# CLK_HMC7043.net
KiCad netlist of a schematic drawn in Altium Designer
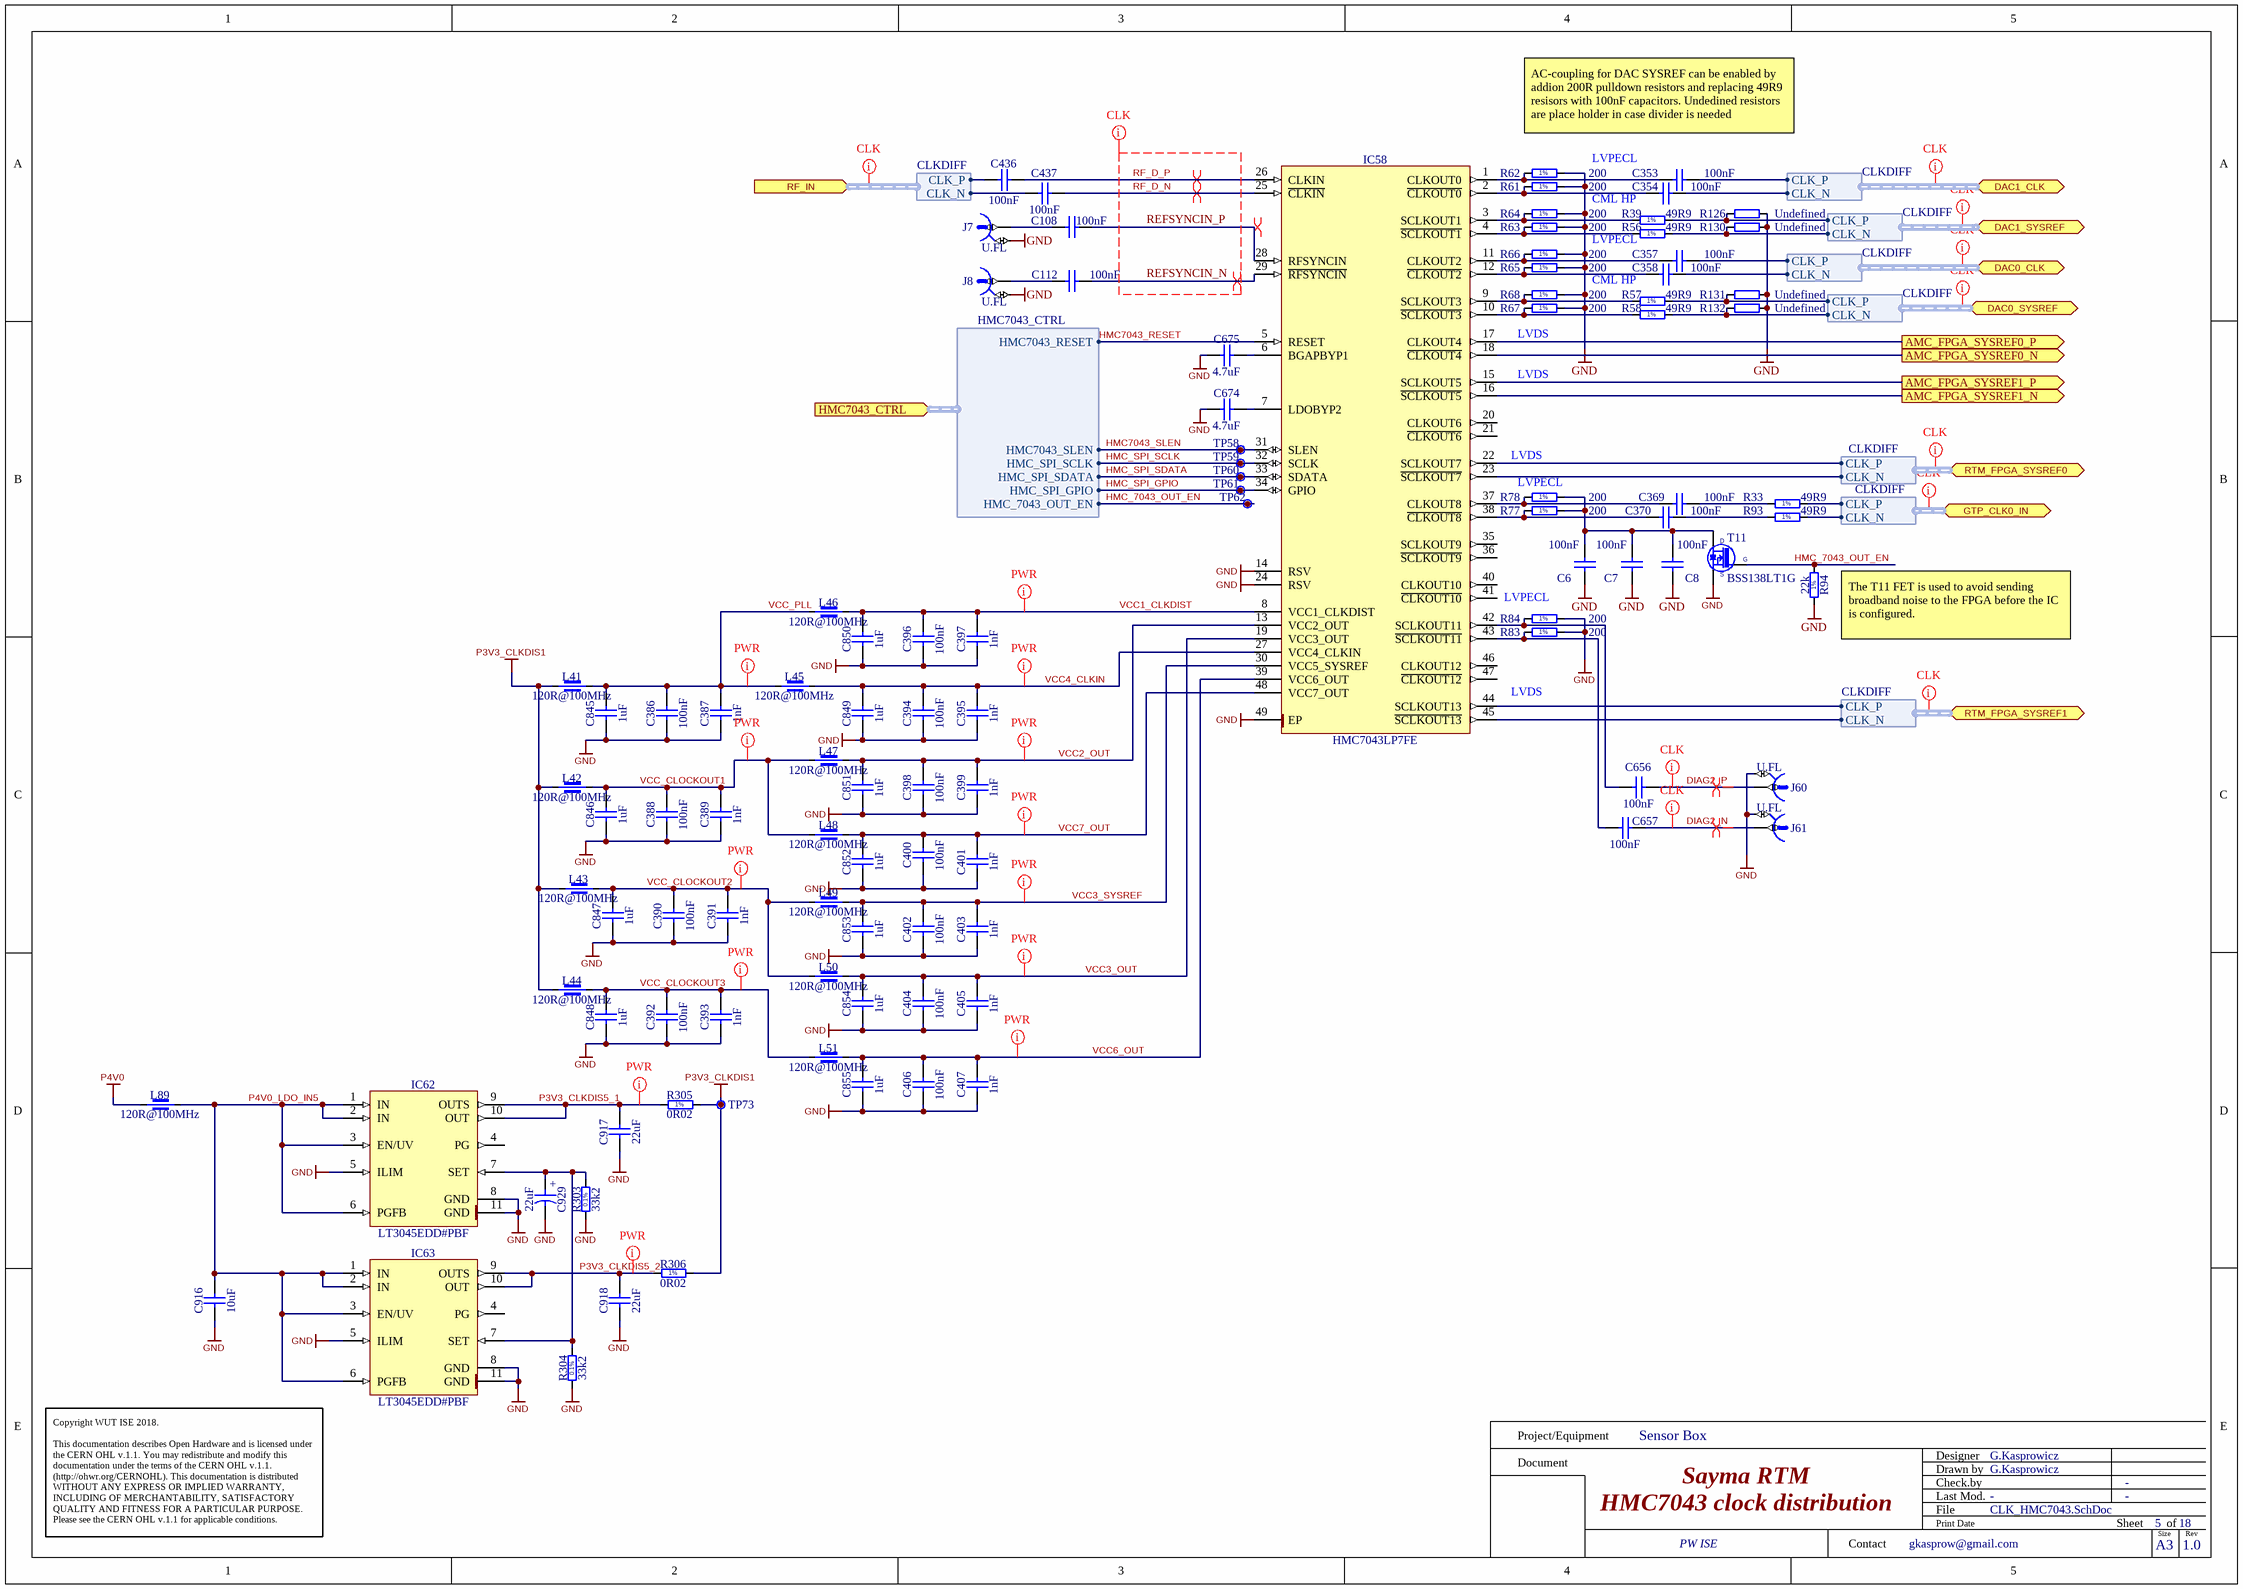
[diagram p0: CLK_HMC7043.SchDoc]

(export (version "E")
  (design (tool "Eeschema 10.0.6"))
  (components
    (comp (ref "C6")
      (value "100nF")
      (footprint "CAPC0603X33N")
      (description "Non-polarised capacitor")
      (fields
        (field (name "MANUFACTURER PART NUMBER") "CC0201_100NF_6.3V_10%_X5R")
        (field (name "MANUFACTURER") "GENERIC")
        (field (name "AUTHOR") "CERN DEM JLC")
      )
      (libsource (lib "Capacitors") (part "Capacitor - non polarized"))
    )
    (comp (ref "C7")
      (value "100nF")
      (footprint "CAPC0603X33N")
      (description "Non-polarised capacitor")
      (fields
        (field (name "MANUFACTURER PART NUMBER") "CC0201_100NF_6.3V_10%_X5R")
        (field (name "MANUFACTURER") "GENERIC")
        (field (name "AUTHOR") "CERN DEM JLC")
      )
      (libsource (lib "Capacitors") (part "Capacitor - non polarized"))
    )
    (comp (ref "C8")
      (value "100nF")
      (footprint "CAPC0603X33N")
      (description "Non-polarised capacitor")
      (fields
        (field (name "MANUFACTURER PART NUMBER") "CC0201_100NF_6.3V_10%_X5R")
        (field (name "MANUFACTURER") "GENERIC")
        (field (name "AUTHOR") "CERN DEM JLC")
      )
      (libsource (lib "Capacitors") (part "Capacitor - non polarized"))
    )
    (comp (ref "C108")
      (value "100nF")
      (footprint "CAPC0603X33N")
      (description "Non-polarised capacitor")
      (fields
        (field (name "MANUFACTURER PART NUMBER") "CC0201_100NF_6.3V_10%_X5R")
        (field (name "MANUFACTURER") "GENERIC")
        (field (name "AUTHOR") "CERN DEM JLC")
      )
      (libsource (lib "Capacitors") (part "Capacitor - non polarized"))
    )
    (comp (ref "C112")
      (value "100nF")
      (footprint "CAPC0603X33N")
      (description "Non-polarised capacitor")
      (fields
        (field (name "MANUFACTURER PART NUMBER") "CC0201_100NF_6.3V_10%_X5R")
        (field (name "MANUFACTURER") "GENERIC")
        (field (name "AUTHOR") "CERN DEM JLC")
      )
      (libsource (lib "Capacitors") (part "Capacitor - non polarized"))
    )
    (comp (ref "C353")
      (value "100nF")
      (footprint "CAPC0603X33N")
      (description "Non-polarised capacitor")
      (fields
        (field (name "MANUFACTURER PART NUMBER") "CC0201_100NF_6.3V_10%_X5R")
        (field (name "MANUFACTURER") "GENERIC")
        (field (name "AUTHOR") "CERN DEM JLC")
      )
      (libsource (lib "Capacitors") (part "Capacitor - non polarized"))
    )
    (comp (ref "C354")
      (value "100nF")
      (footprint "CAPC0603X33N")
      (description "Non-polarised capacitor")
      (fields
        (field (name "MANUFACTURER PART NUMBER") "CC0201_100NF_6.3V_10%_X5R")
        (field (name "MANUFACTURER") "GENERIC")
        (field (name "AUTHOR") "CERN DEM JLC")
      )
      (libsource (lib "Capacitors") (part "Capacitor - non polarized"))
    )
    (comp (ref "C357")
      (value "100nF")
      (footprint "CAPC0603X33N")
      (description "Non-polarised capacitor")
      (fields
        (field (name "MANUFACTURER PART NUMBER") "CC0201_100NF_6.3V_10%_X5R")
        (field (name "MANUFACTURER") "GENERIC")
        (field (name "AUTHOR") "CERN DEM JLC")
      )
      (libsource (lib "Capacitors") (part "Capacitor - non polarized"))
    )
    (comp (ref "C358")
      (value "100nF")
      (footprint "CAPC0603X33N")
      (description "Non-polarised capacitor")
      (fields
        (field (name "MANUFACTURER PART NUMBER") "CC0201_100NF_6.3V_10%_X5R")
        (field (name "MANUFACTURER") "GENERIC")
        (field (name "AUTHOR") "CERN DEM JLC")
      )
      (libsource (lib "Capacitors") (part "Capacitor - non polarized"))
    )
    (comp (ref "C369")
      (value "100nF")
      (footprint "CAPC0603X33N")
      (description "Non-polarised capacitor")
      (fields
        (field (name "MANUFACTURER PART NUMBER") "CC0201_100NF_6.3V_10%_X5R")
        (field (name "MANUFACTURER") "GENERIC")
        (field (name "AUTHOR") "CERN DEM JLC")
      )
      (libsource (lib "Capacitors") (part "Capacitor - non polarized"))
    )
    (comp (ref "C370")
      (value "100nF")
      (footprint "CAPC0603X33N")
      (description "Non-polarised capacitor")
      (fields
        (field (name "MANUFACTURER PART NUMBER") "CC0201_100NF_6.3V_10%_X5R")
        (field (name "MANUFACTURER") "GENERIC")
        (field (name "AUTHOR") "CERN DEM JLC")
      )
      (libsource (lib "Capacitors") (part "Capacitor - non polarized"))
    )
    (comp (ref "C386")
      (value "100nF")
      (footprint "CAPC0603X33N")
      (description "Non-polarised capacitor")
      (fields
        (field (name "MANUFACTURER PART NUMBER") "CC0201_100NF_6.3V_10%_X5R")
        (field (name "MANUFACTURER") "GENERIC")
        (field (name "AUTHOR") "CERN DEM JLC")
      )
      (libsource (lib "Capacitors") (part "Capacitor - non polarized"))
    )
    (comp (ref "C387")
      (value "1nF")
      (footprint "CAPC0603X33N")
      (description "Non-polarised capacitor")
      (fields
        (field (name "MANUFACTURER PART NUMBER") "CC0201_1NF_16V_10%_X5R")
        (field (name "MANUFACTURER") "GENERIC")
        (field (name "AUTHOR") "CERN DEM JLC")
      )
      (libsource (lib "Capacitors") (part "Capacitor - non polarized"))
    )
    (comp (ref "C388")
      (value "100nF")
      (footprint "CAPC0603X33N")
      (description "Non-polarised capacitor")
      (fields
        (field (name "MANUFACTURER PART NUMBER") "CC0201_100NF_6.3V_10%_X5R")
        (field (name "MANUFACTURER") "GENERIC")
        (field (name "AUTHOR") "CERN DEM JLC")
      )
      (libsource (lib "Capacitors") (part "Capacitor - non polarized"))
    )
    (comp (ref "C389")
      (value "1nF")
      (footprint "CAPC0603X33N")
      (description "Non-polarised capacitor")
      (fields
        (field (name "MANUFACTURER PART NUMBER") "CC0201_1NF_16V_10%_X5R")
        (field (name "MANUFACTURER") "GENERIC")
        (field (name "AUTHOR") "CERN DEM JLC")
      )
      (libsource (lib "Capacitors") (part "Capacitor - non polarized"))
    )
    (comp (ref "C390")
      (value "100nF")
      (footprint "CAPC0603X33N")
      (description "Non-polarised capacitor")
      (fields
        (field (name "MANUFACTURER PART NUMBER") "CC0201_100NF_6.3V_10%_X5R")
        (field (name "MANUFACTURER") "GENERIC")
        (field (name "AUTHOR") "CERN DEM JLC")
      )
      (libsource (lib "Capacitors") (part "Capacitor - non polarized"))
    )
    (comp (ref "C391")
      (value "1nF")
      (footprint "CAPC0603X33N")
      (description "Non-polarised capacitor")
      (fields
        (field (name "MANUFACTURER PART NUMBER") "CC0201_1NF_16V_10%_X5R")
        (field (name "MANUFACTURER") "GENERIC")
        (field (name "AUTHOR") "CERN DEM JLC")
      )
      (libsource (lib "Capacitors") (part "Capacitor - non polarized"))
    )
    (comp (ref "C392")
      (value "100nF")
      (footprint "CAPC0603X33N")
      (description "Non-polarised capacitor")
      (fields
        (field (name "MANUFACTURER PART NUMBER") "CC0201_100NF_6.3V_10%_X5R")
        (field (name "MANUFACTURER") "GENERIC")
        (field (name "AUTHOR") "CERN DEM JLC")
      )
      (libsource (lib "Capacitors") (part "Capacitor - non polarized"))
    )
    (comp (ref "C393")
      (value "1nF")
      (footprint "CAPC0603X33N")
      (description "Non-polarised capacitor")
      (fields
        (field (name "MANUFACTURER PART NUMBER") "CC0201_1NF_16V_10%_X5R")
        (field (name "MANUFACTURER") "GENERIC")
        (field (name "AUTHOR") "CERN DEM JLC")
      )
      (libsource (lib "Capacitors") (part "Capacitor - non polarized"))
    )
    (comp (ref "C394")
      (value "100nF")
      (footprint "CAPC0603X33N")
      (description "Non-polarised capacitor")
      (fields
        (field (name "MANUFACTURER PART NUMBER") "CC0201_100NF_6.3V_10%_X5R")
        (field (name "MANUFACTURER") "GENERIC")
        (field (name "AUTHOR") "CERN DEM JLC")
      )
      (libsource (lib "Capacitors") (part "Capacitor - non polarized"))
    )
    (comp (ref "C395")
      (value "1nF")
      (footprint "CAPC0603X33N")
      (description "Non-polarised capacitor")
      (fields
        (field (name "MANUFACTURER PART NUMBER") "CC0201_1NF_16V_10%_X5R")
        (field (name "MANUFACTURER") "GENERIC")
        (field (name "AUTHOR") "CERN DEM JLC")
      )
      (libsource (lib "Capacitors") (part "Capacitor - non polarized"))
    )
    (comp (ref "C396")
      (value "100nF")
      (footprint "CAPC0603X33N")
      (description "Non-polarised capacitor")
      (fields
        (field (name "MANUFACTURER PART NUMBER") "CC0201_100NF_6.3V_10%_X5R")
        (field (name "MANUFACTURER") "GENERIC")
        (field (name "AUTHOR") "CERN DEM JLC")
      )
      (libsource (lib "Capacitors") (part "Capacitor - non polarized"))
    )
    (comp (ref "C397")
      (value "1nF")
      (footprint "CAPC0603X33N")
      (description "Non-polarised capacitor")
      (fields
        (field (name "MANUFACTURER PART NUMBER") "CC0201_1NF_16V_10%_X5R")
        (field (name "MANUFACTURER") "GENERIC")
        (field (name "AUTHOR") "CERN DEM JLC")
      )
      (libsource (lib "Capacitors") (part "Capacitor - non polarized"))
    )
    (comp (ref "C398")
      (value "100nF")
      (footprint "CAPC0603X33N")
      (description "Non-polarised capacitor")
      (fields
        (field (name "MANUFACTURER PART NUMBER") "CC0201_100NF_6.3V_10%_X5R")
        (field (name "MANUFACTURER") "GENERIC")
        (field (name "AUTHOR") "CERN DEM JLC")
      )
      (libsource (lib "Capacitors") (part "Capacitor - non polarized"))
    )
    (comp (ref "C399")
      (value "1nF")
      (footprint "CAPC0603X33N")
      (description "Non-polarised capacitor")
      (fields
        (field (name "MANUFACTURER PART NUMBER") "CC0201_1NF_16V_10%_X5R")
        (field (name "MANUFACTURER") "GENERIC")
        (field (name "AUTHOR") "CERN DEM JLC")
      )
      (libsource (lib "Capacitors") (part "Capacitor - non polarized"))
    )
    (comp (ref "C400")
      (value "100nF")
      (footprint "CAPC0603X33N")
      (description "Non-polarised capacitor")
      (fields
        (field (name "MANUFACTURER PART NUMBER") "CC0201_100NF_6.3V_10%_X5R")
        (field (name "MANUFACTURER") "GENERIC")
        (field (name "AUTHOR") "CERN DEM JLC")
      )
      (libsource (lib "Capacitors") (part "Capacitor - non polarized"))
    )
    (comp (ref "C401")
      (value "1nF")
      (footprint "CAPC0603X33N")
      (description "Non-polarised capacitor")
      (fields
        (field (name "MANUFACTURER PART NUMBER") "CC0201_1NF_16V_10%_X5R")
        (field (name "MANUFACTURER") "GENERIC")
        (field (name "AUTHOR") "CERN DEM JLC")
      )
      (libsource (lib "Capacitors") (part "Capacitor - non polarized"))
    )
    (comp (ref "C402")
      (value "100nF")
      (footprint "CAPC0603X33N")
      (description "Non-polarised capacitor")
      (fields
        (field (name "MANUFACTURER PART NUMBER") "CC0201_100NF_6.3V_10%_X5R")
        (field (name "MANUFACTURER") "GENERIC")
        (field (name "AUTHOR") "CERN DEM JLC")
      )
      (libsource (lib "Capacitors") (part "Capacitor - non polarized"))
    )
    (comp (ref "C403")
      (value "1nF")
      (footprint "CAPC0603X33N")
      (description "Non-polarised capacitor")
      (fields
        (field (name "MANUFACTURER PART NUMBER") "CC0201_1NF_16V_10%_X5R")
        (field (name "MANUFACTURER") "GENERIC")
        (field (name "AUTHOR") "CERN DEM JLC")
      )
      (libsource (lib "Capacitors") (part "Capacitor - non polarized"))
    )
    (comp (ref "C404")
      (value "100nF")
      (footprint "CAPC0603X33N")
      (description "Non-polarised capacitor")
      (fields
        (field (name "MANUFACTURER PART NUMBER") "CC0201_100NF_6.3V_10%_X5R")
        (field (name "MANUFACTURER") "GENERIC")
        (field (name "AUTHOR") "CERN DEM JLC")
      )
      (libsource (lib "Capacitors") (part "Capacitor - non polarized"))
    )
    (comp (ref "C405")
      (value "1nF")
      (footprint "CAPC0603X33N")
      (description "Non-polarised capacitor")
      (fields
        (field (name "MANUFACTURER PART NUMBER") "CC0201_1NF_16V_10%_X5R")
        (field (name "MANUFACTURER") "GENERIC")
        (field (name "AUTHOR") "CERN DEM JLC")
      )
      (libsource (lib "Capacitors") (part "Capacitor - non polarized"))
    )
    (comp (ref "C406")
      (value "100nF")
      (footprint "CAPC0603X33N")
      (description "Non-polarised capacitor")
      (fields
        (field (name "MANUFACTURER PART NUMBER") "CC0201_100NF_6.3V_10%_X5R")
        (field (name "MANUFACTURER") "GENERIC")
        (field (name "AUTHOR") "CERN DEM JLC")
      )
      (libsource (lib "Capacitors") (part "Capacitor - non polarized"))
    )
    (comp (ref "C407")
      (value "1nF")
      (footprint "CAPC0603X33N")
      (description "Non-polarised capacitor")
      (fields
        (field (name "MANUFACTURER PART NUMBER") "CC0201_1NF_16V_10%_X5R")
        (field (name "MANUFACTURER") "GENERIC")
        (field (name "AUTHOR") "CERN DEM JLC")
      )
      (libsource (lib "Capacitors") (part "Capacitor - non polarized"))
    )
    (comp (ref "C436")
      (value "100nF")
      (footprint "CAPC0603X33N")
      (description "Non-polarised capacitor")
      (fields
        (field (name "MANUFACTURER PART NUMBER") "CC0201_100NF_6.3V_10%_X5R")
        (field (name "MANUFACTURER") "GENERIC")
        (field (name "AUTHOR") "CERN DEM JLC")
      )
      (libsource (lib "Capacitors") (part "Capacitor - non polarized"))
    )
    (comp (ref "C437")
      (value "100nF")
      (footprint "CAPC0603X33N")
      (description "Non-polarised capacitor")
      (fields
        (field (name "MANUFACTURER PART NUMBER") "CC0201_100NF_6.3V_10%_X5R")
        (field (name "MANUFACTURER") "GENERIC")
        (field (name "AUTHOR") "CERN DEM JLC")
      )
      (libsource (lib "Capacitors") (part "Capacitor - non polarized"))
    )
    (comp (ref "C656")
      (value "100nF")
      (footprint "CAPC0603X33N")
      (description "Non-polarised capacitor")
      (fields
        (field (name "MANUFACTURER PART NUMBER") "CC0201_100NF_6.3V_10%_X5R")
        (field (name "MANUFACTURER") "GENERIC")
        (field (name "AUTHOR") "CERN DEM JLC")
      )
      (libsource (lib "Capacitors") (part "Capacitor - non polarized"))
    )
    (comp (ref "C657")
      (value "100nF")
      (footprint "CAPC0603X33N")
      (description "Non-polarised capacitor")
      (fields
        (field (name "MANUFACTURER PART NUMBER") "CC0201_100NF_6.3V_10%_X5R")
        (field (name "MANUFACTURER") "GENERIC")
        (field (name "AUTHOR") "CERN DEM JLC")
      )
      (libsource (lib "Capacitors") (part "Capacitor - non polarized"))
    )
    (comp (ref "C674")
      (value "4.7uF")
      (footprint "CAPC1608X90N")
      (description "Non-polarised capacitor")
      (fields
        (field (name "MANUFACTURER PART NUMBER") "CC0603_4.7UF_25V_10%_X5R")
        (field (name "MANUFACTURER") "GENERIC")
        (field (name "AUTHOR") "CERN DEM JLC")
      )
      (libsource (lib "Capacitors") (part "Capacitor - non polarized"))
    )
    (comp (ref "C675")
      (value "4.7uF")
      (footprint "CAPC1608X90N")
      (description "Non-polarised capacitor")
      (fields
        (field (name "MANUFACTURER PART NUMBER") "CC0603_4.7UF_25V_10%_X5R")
        (field (name "MANUFACTURER") "GENERIC")
        (field (name "AUTHOR") "CERN DEM JLC")
      )
      (libsource (lib "Capacitors") (part "Capacitor - non polarized"))
    )
    (comp (ref "C845")
      (value "1uF")
      (footprint "CAPC1005X55N")
      (description "Non-polarised capacitor")
      (fields
        (field (name "MANUFACTURER PART NUMBER") "CC0402_1UF_16V_10%_X5R")
        (field (name "MANUFACTURER") "GENERIC")
        (field (name "AUTHOR") "CERN DEM JLC")
      )
      (libsource (lib "Capacitors") (part "Capacitor - non polarized"))
    )
    (comp (ref "C846")
      (value "1uF")
      (footprint "CAPC1005X55N")
      (description "Non-polarised capacitor")
      (fields
        (field (name "MANUFACTURER PART NUMBER") "CC0402_1UF_16V_10%_X5R")
        (field (name "MANUFACTURER") "GENERIC")
        (field (name "AUTHOR") "CERN DEM JLC")
      )
      (libsource (lib "Capacitors") (part "Capacitor - non polarized"))
    )
    (comp (ref "C847")
      (value "1uF")
      (footprint "CAPC1005X55N")
      (description "Non-polarised capacitor")
      (fields
        (field (name "MANUFACTURER PART NUMBER") "CC0402_1UF_16V_10%_X5R")
        (field (name "MANUFACTURER") "GENERIC")
        (field (name "AUTHOR") "CERN DEM JLC")
      )
      (libsource (lib "Capacitors") (part "Capacitor - non polarized"))
    )
    (comp (ref "C848")
      (value "1uF")
      (footprint "CAPC1005X55N")
      (description "Non-polarised capacitor")
      (fields
        (field (name "MANUFACTURER PART NUMBER") "CC0402_1UF_16V_10%_X5R")
        (field (name "MANUFACTURER") "GENERIC")
        (field (name "AUTHOR") "CERN DEM JLC")
      )
      (libsource (lib "Capacitors") (part "Capacitor - non polarized"))
    )
    (comp (ref "C849")
      (value "1uF")
      (footprint "CAPC1005X55N")
      (description "Non-polarised capacitor")
      (fields
        (field (name "MANUFACTURER PART NUMBER") "CC0402_1UF_16V_10%_X5R")
        (field (name "MANUFACTURER") "GENERIC")
        (field (name "AUTHOR") "CERN DEM JLC")
      )
      (libsource (lib "Capacitors") (part "Capacitor - non polarized"))
    )
    (comp (ref "C850")
      (value "1uF")
      (footprint "CAPC1005X55N")
      (description "Non-polarised capacitor")
      (fields
        (field (name "MANUFACTURER PART NUMBER") "CC0402_1UF_16V_10%_X5R")
        (field (name "MANUFACTURER") "GENERIC")
        (field (name "AUTHOR") "CERN DEM JLC")
      )
      (libsource (lib "Capacitors") (part "Capacitor - non polarized"))
    )
    (comp (ref "C851")
      (value "1uF")
      (footprint "CAPC1005X55N")
      (description "Non-polarised capacitor")
      (fields
        (field (name "MANUFACTURER PART NUMBER") "CC0402_1UF_16V_10%_X5R")
        (field (name "MANUFACTURER") "GENERIC")
        (field (name "AUTHOR") "CERN DEM JLC")
      )
      (libsource (lib "Capacitors") (part "Capacitor - non polarized"))
    )
    (comp (ref "C852")
      (value "1uF")
      (footprint "CAPC1005X55N")
      (description "Non-polarised capacitor")
      (fields
        (field (name "MANUFACTURER PART NUMBER") "CC0402_1UF_16V_10%_X5R")
        (field (name "MANUFACTURER") "GENERIC")
        (field (name "AUTHOR") "CERN DEM JLC")
      )
      (libsource (lib "Capacitors") (part "Capacitor - non polarized"))
    )
    (comp (ref "C853")
      (value "1uF")
      (footprint "CAPC1005X55N")
      (description "Non-polarised capacitor")
      (fields
        (field (name "MANUFACTURER PART NUMBER") "CC0402_1UF_16V_10%_X5R")
        (field (name "MANUFACTURER") "GENERIC")
        (field (name "AUTHOR") "CERN DEM JLC")
      )
      (libsource (lib "Capacitors") (part "Capacitor - non polarized"))
    )
    (comp (ref "C854")
      (value "1uF")
      (footprint "CAPC1005X55N")
      (description "Non-polarised capacitor")
      (fields
        (field (name "MANUFACTURER PART NUMBER") "CC0402_1UF_16V_10%_X5R")
        (field (name "MANUFACTURER") "GENERIC")
        (field (name "AUTHOR") "CERN DEM JLC")
      )
      (libsource (lib "Capacitors") (part "Capacitor - non polarized"))
    )
    (comp (ref "C855")
      (value "1uF")
      (footprint "CAPC1005X55N")
      (description "Non-polarised capacitor")
      (fields
        (field (name "MANUFACTURER PART NUMBER") "CC0402_1UF_16V_10%_X5R")
        (field (name "MANUFACTURER") "GENERIC")
        (field (name "AUTHOR") "CERN DEM JLC")
      )
      (libsource (lib "Capacitors") (part "Capacitor - non polarized"))
    )
    (comp (ref "C916")
      (value "10uF")
      (footprint "CAPC1608X87N")
      (description "Non-polarised capacitor")
      (fields
        (field (name "MANUFACTURER PART NUMBER") "CC0603_10uF_6.3V_20%_X5R")
        (field (name "MANUFACTURER") "GENERIC")
        (field (name "AUTHOR") "CERN DEM JLC")
      )
      (libsource (lib "Capacitors") (part "Capacitor - non polarized"))
    )
    (comp (ref "C917")
      (value "22uF")
      (footprint "CAPC2012X135N")
      (description "Non-polarised capacitor")
      (fields
        (field (name "MANUFACTURER PART NUMBER") "CC0805_22UF_16V_10%_X5R")
        (field (name "MANUFACTURER") "GENERIC")
        (field (name "AUTHOR") "CERN DEM JLC")
      )
      (libsource (lib "Capacitors") (part "Capacitor - non polarized"))
    )
    (comp (ref "C918")
      (value "22uF")
      (footprint "CAPC2012X135N")
      (description "Non-polarised capacitor")
      (fields
        (field (name "MANUFACTURER PART NUMBER") "CC0805_22UF_16V_10%_X5R")
        (field (name "MANUFACTURER") "GENERIC")
        (field (name "AUTHOR") "CERN DEM JLC")
      )
      (libsource (lib "Capacitors") (part "Capacitor - non polarized"))
    )
    (comp (ref "C929")
      (value "22uF")
      (footprint "CAPMP3216X180N")
      (description "Polarised capacitor")
      (fields
        (field (name "MANUFACTURER PART NUMBER") "CTE3216-18_22UF_6.3V_10%_LESR0900")
        (field (name "MANUFACTURER") "GENERIC")
        (field (name "AUTHOR") "CERN DEM JLC")
      )
      (libsource (lib "Capacitors") (part "Capacitor - polarized"))
    )
    (comp (ref "IC58")
      (value "HMC7043LP7FE")
      (footprint "QFN50P700X700X100-49N-S565")
      (description "High Performance, 3.2 GHz, 14-Output Fanout Buffer")
      (fields (field (name "MANUFACTURER") "ANALOG DEVICES") (field (name "AUTHOR") "CERN DEM BC"))
      (libsource (lib "ICs And Semiconductors") (part "HMC7043LP7FE"))
    )
    (comp (ref "IC62")
      (value "LT3045EDD#PBF")
      (footprint "SON50P300X300X80-11N-R175X248")
      (description "20V, 500mA, Ultralow Noise, Ultrahigh PSRR Linear Regulator")
      (fields (field (name "MANUFACTURER") "LINEAR TECHNOLOGY") (field (name "AUTHOR") "CERN DEM JLC"))
      (libsource (lib "ICs And Semiconductors") (part "LT3045EDD"))
    )
    (comp (ref "IC63")
      (value "LT3045EDD#PBF")
      (footprint "SON50P300X300X80-11N-R175X248")
      (description "20V, 500mA, Ultralow Noise, Ultrahigh PSRR Linear Regulator")
      (fields (field (name "MANUFACTURER") "LINEAR TECHNOLOGY") (field (name "AUTHOR") "CERN DEM JLC"))
      (libsource (lib "ICs And Semiconductors") (part "LT3045EDD"))
    )
    (comp (ref "J7")
      (value "U.FL")
      (footprint "HIROSE_U.FL-R-SMT-1(10)")
      (fields
        (field (name "MANUFACTURER PART NUMBER") "U.FL-R-SMT-1(10)")
        (field (name "MANUFACTURER") "HIROSE (HRS)")
        (field (name "PART NUMBER") "HIROSE_U.FL-R-SMT-1(10)")
        (field (name "AUTHOR") "CERN DEM JLC")
      )
      (libsource (lib "Connectors") (part "Coax_1Male_1Shield"))
    )
    (comp (ref "J8")
      (value "U.FL")
      (footprint "HIROSE_U.FL-R-SMT-1(10)")
      (fields
        (field (name "MANUFACTURER PART NUMBER") "U.FL-R-SMT-1(10)")
        (field (name "MANUFACTURER") "HIROSE (HRS)")
        (field (name "PART NUMBER") "HIROSE_U.FL-R-SMT-1(10)")
        (field (name "AUTHOR") "CERN DEM JLC")
      )
      (libsource (lib "Connectors") (part "Coax_1Male_1Shield"))
    )
    (comp (ref "J60")
      (value "U.FL")
      (footprint "HIROSE_U.FL-R-SMT-1(10)")
      (fields
        (field (name "MANUFACTURER PART NUMBER") "U.FL-R-SMT-1(10)")
        (field (name "MANUFACTURER") "HIROSE (HRS)")
        (field (name "PART NUMBER") "HIROSE_U.FL-R-SMT-1(10)")
        (field (name "AUTHOR") "CERN DEM JLC")
      )
      (libsource (lib "Connectors") (part "Coax_1Male_1Shield"))
    )
    (comp (ref "J61")
      (value "U.FL")
      (footprint "HIROSE_U.FL-R-SMT-1(10)")
      (fields
        (field (name "MANUFACTURER PART NUMBER") "U.FL-R-SMT-1(10)")
        (field (name "MANUFACTURER") "HIROSE (HRS)")
        (field (name "PART NUMBER") "HIROSE_U.FL-R-SMT-1(10)")
        (field (name "AUTHOR") "CERN DEM JLC")
      )
      (libsource (lib "Connectors") (part "Coax_1Male_1Shield"))
    )
    (comp (ref "L41")
      (value "120R@100MHz")
      (footprint "INDC1608X95N")
      (fields
        (field (name "MANUFACTURER PART NUMBER") "BLM18PG121SN1D")
        (field (name "MANUFACTURER") "MURATA")
        (field (name "PART NUMBER") "IND0603_MURATA_BLM18PG121SN1D")
        (field (name "AUTHOR") "CERN DEM BC")
      )
      (libsource (lib "Inductors & Transformers") (part "Ferrite Bead"))
    )
    (comp (ref "L42")
      (value "120R@100MHz")
      (footprint "INDC1608X95N")
      (fields
        (field (name "MANUFACTURER PART NUMBER") "BLM18PG121SN1D")
        (field (name "MANUFACTURER") "MURATA")
        (field (name "PART NUMBER") "IND0603_MURATA_BLM18PG121SN1D")
        (field (name "AUTHOR") "CERN DEM BC")
      )
      (libsource (lib "Inductors & Transformers") (part "Ferrite Bead"))
    )
    (comp (ref "L43")
      (value "120R@100MHz")
      (footprint "INDC1608X95N")
      (fields
        (field (name "MANUFACTURER PART NUMBER") "BLM18PG121SN1D")
        (field (name "MANUFACTURER") "MURATA")
        (field (name "PART NUMBER") "IND0603_MURATA_BLM18PG121SN1D")
        (field (name "AUTHOR") "CERN DEM BC")
      )
      (libsource (lib "Inductors & Transformers") (part "Ferrite Bead"))
    )
    (comp (ref "L44")
      (value "120R@100MHz")
      (footprint "INDC1608X95N")
      (fields
        (field (name "MANUFACTURER PART NUMBER") "BLM18PG121SN1D")
        (field (name "MANUFACTURER") "MURATA")
        (field (name "PART NUMBER") "IND0603_MURATA_BLM18PG121SN1D")
        (field (name "AUTHOR") "CERN DEM BC")
      )
      (libsource (lib "Inductors & Transformers") (part "Ferrite Bead"))
    )
    (comp (ref "L45")
      (value "120R@100MHz")
      (footprint "INDC1608X95N")
      (fields
        (field (name "MANUFACTURER PART NUMBER") "BLM18PG121SN1D")
        (field (name "MANUFACTURER") "MURATA")
        (field (name "PART NUMBER") "IND0603_MURATA_BLM18PG121SN1D")
        (field (name "AUTHOR") "CERN DEM BC")
      )
      (libsource (lib "Inductors & Transformers") (part "Ferrite Bead"))
    )
    (comp (ref "L46")
      (value "120R@100MHz")
      (footprint "INDC1608X95N")
      (fields
        (field (name "MANUFACTURER PART NUMBER") "BLM18PG121SN1D")
        (field (name "MANUFACTURER") "MURATA")
        (field (name "PART NUMBER") "IND0603_MURATA_BLM18PG121SN1D")
        (field (name "AUTHOR") "CERN DEM BC")
      )
      (libsource (lib "Inductors & Transformers") (part "Ferrite Bead"))
    )
    (comp (ref "L47")
      (value "120R@100MHz")
      (footprint "INDC1608X95N")
      (fields
        (field (name "MANUFACTURER PART NUMBER") "BLM18PG121SN1D")
        (field (name "MANUFACTURER") "MURATA")
        (field (name "PART NUMBER") "IND0603_MURATA_BLM18PG121SN1D")
        (field (name "AUTHOR") "CERN DEM BC")
      )
      (libsource (lib "Inductors & Transformers") (part "Ferrite Bead"))
    )
    (comp (ref "L48")
      (value "120R@100MHz")
      (footprint "INDC1608X95N")
      (fields
        (field (name "MANUFACTURER PART NUMBER") "BLM18PG121SN1D")
        (field (name "MANUFACTURER") "MURATA")
        (field (name "PART NUMBER") "IND0603_MURATA_BLM18PG121SN1D")
        (field (name "AUTHOR") "CERN DEM BC")
      )
      (libsource (lib "Inductors & Transformers") (part "Ferrite Bead"))
    )
    (comp (ref "L49")
      (value "120R@100MHz")
      (footprint "INDC1608X95N")
      (fields
        (field (name "MANUFACTURER PART NUMBER") "BLM18PG121SN1D")
        (field (name "MANUFACTURER") "MURATA")
        (field (name "PART NUMBER") "IND0603_MURATA_BLM18PG121SN1D")
        (field (name "AUTHOR") "CERN DEM BC")
      )
      (libsource (lib "Inductors & Transformers") (part "Ferrite Bead"))
    )
    (comp (ref "L50")
      (value "120R@100MHz")
      (footprint "INDC1608X95N")
      (fields
        (field (name "MANUFACTURER PART NUMBER") "BLM18PG121SN1D")
        (field (name "MANUFACTURER") "MURATA")
        (field (name "PART NUMBER") "IND0603_MURATA_BLM18PG121SN1D")
        (field (name "AUTHOR") "CERN DEM BC")
      )
      (libsource (lib "Inductors & Transformers") (part "Ferrite Bead"))
    )
    (comp (ref "L51")
      (value "120R@100MHz")
      (footprint "INDC1608X95N")
      (fields
        (field (name "MANUFACTURER PART NUMBER") "BLM18PG121SN1D")
        (field (name "MANUFACTURER") "MURATA")
        (field (name "PART NUMBER") "IND0603_MURATA_BLM18PG121SN1D")
        (field (name "AUTHOR") "CERN DEM BC")
      )
      (libsource (lib "Inductors & Transformers") (part "Ferrite Bead"))
    )
    (comp (ref "L89")
      (value "120R@100MHz")
      (footprint "INDC1608X95N")
      (fields
        (field (name "MANUFACTURER PART NUMBER") "BLM18PG121SN1D")
        (field (name "MANUFACTURER") "MURATA")
        (field (name "PART NUMBER") "IND0603_MURATA_BLM18PG121SN1D")
        (field (name "AUTHOR") "CERN DEM BC")
      )
      (libsource (lib "Inductors & Transformers") (part "Ferrite Bead"))
    )
    (comp (ref "R33")
      (value "49R9")
      (footprint "RESC1005X40N")
      (description "Resistor - 1%")
      (fields
        (field (name "MANUFACTURER PART NUMBER") "R0402_49R9_1%_0.0625W_100PPM")
        (field (name "MANUFACTURER") "GENERIC")
        (field (name "AUTHOR") "CERN DEM JLC")
      )
      (libsource (lib "Resistors") (part "Resistor - 1%"))
    )
    (comp (ref "R39")
      (value "49R9")
      (footprint "RESC1005X40N")
      (description "Resistor - 1%")
      (fields
        (field (name "MANUFACTURER PART NUMBER") "R0402_49R9_1%_0.0625W_100PPM")
        (field (name "MANUFACTURER") "GENERIC")
        (field (name "AUTHOR") "CERN DEM JLC")
      )
      (libsource (lib "Resistors") (part "Resistor - 1%"))
    )
    (comp (ref "R56")
      (value "49R9")
      (footprint "RESC1005X40N")
      (description "Resistor - 1%")
      (fields
        (field (name "MANUFACTURER PART NUMBER") "R0402_49R9_1%_0.0625W_100PPM")
        (field (name "MANUFACTURER") "GENERIC")
        (field (name "AUTHOR") "CERN DEM JLC")
      )
      (libsource (lib "Resistors") (part "Resistor - 1%"))
    )
    (comp (ref "R57")
      (value "49R9")
      (footprint "RESC1005X40N")
      (description "Resistor - 1%")
      (fields
        (field (name "MANUFACTURER PART NUMBER") "R0402_49R9_1%_0.0625W_100PPM")
        (field (name "MANUFACTURER") "GENERIC")
        (field (name "AUTHOR") "CERN DEM JLC")
      )
      (libsource (lib "Resistors") (part "Resistor - 1%"))
    )
    (comp (ref "R58")
      (value "49R9")
      (footprint "RESC1005X40N")
      (description "Resistor - 1%")
      (fields
        (field (name "MANUFACTURER PART NUMBER") "R0402_49R9_1%_0.0625W_100PPM")
        (field (name "MANUFACTURER") "GENERIC")
        (field (name "AUTHOR") "CERN DEM JLC")
      )
      (libsource (lib "Resistors") (part "Resistor - 1%"))
    )
    (comp (ref "R61")
      (value "200")
      (footprint "RESC1005X40N")
      (description "Resistor - 1%")
      (fields
        (field (name "MANUFACTURER PART NUMBER") "R0402_200R_1%_0.0625W_100PPM")
        (field (name "MANUFACTURER") "GENERIC")
        (field (name "AUTHOR") "CERN DEM JLC")
      )
      (libsource (lib "Resistors") (part "Resistor - 1%"))
    )
    (comp (ref "R62")
      (value "200")
      (footprint "RESC1005X40N")
      (description "Resistor - 1%")
      (fields
        (field (name "MANUFACTURER PART NUMBER") "R0402_200R_1%_0.0625W_100PPM")
        (field (name "MANUFACTURER") "GENERIC")
        (field (name "AUTHOR") "CERN DEM JLC")
      )
      (libsource (lib "Resistors") (part "Resistor - 1%"))
    )
    (comp (ref "R63")
      (value "200")
      (footprint "RESC1005X40N")
      (description "Resistor - 1%")
      (fields
        (field (name "MANUFACTURER PART NUMBER") "R0402_200R_1%_0.0625W_100PPM")
        (field (name "MANUFACTURER") "GENERIC")
        (field (name "AUTHOR") "CERN DEM JLC")
      )
      (libsource (lib "Resistors") (part "Resistor - 1%"))
    )
    (comp (ref "R64")
      (value "200")
      (footprint "RESC1005X40N")
      (description "Resistor - 1%")
      (fields
        (field (name "MANUFACTURER PART NUMBER") "R0402_200R_1%_0.0625W_100PPM")
        (field (name "MANUFACTURER") "GENERIC")
        (field (name "AUTHOR") "CERN DEM JLC")
      )
      (libsource (lib "Resistors") (part "Resistor - 1%"))
    )
    (comp (ref "R65")
      (value "200")
      (footprint "RESC1005X40N")
      (description "Resistor - 1%")
      (fields
        (field (name "MANUFACTURER PART NUMBER") "R0402_200R_1%_0.0625W_100PPM")
        (field (name "MANUFACTURER") "GENERIC")
        (field (name "AUTHOR") "CERN DEM JLC")
      )
      (libsource (lib "Resistors") (part "Resistor - 1%"))
    )
    (comp (ref "R66")
      (value "200")
      (footprint "RESC1005X40N")
      (description "Resistor - 1%")
      (fields
        (field (name "MANUFACTURER PART NUMBER") "R0402_200R_1%_0.0625W_100PPM")
        (field (name "MANUFACTURER") "GENERIC")
        (field (name "AUTHOR") "CERN DEM JLC")
      )
      (libsource (lib "Resistors") (part "Resistor - 1%"))
    )
    (comp (ref "R67")
      (value "200")
      (footprint "RESC1005X40N")
      (description "Resistor - 1%")
      (fields
        (field (name "MANUFACTURER PART NUMBER") "R0402_200R_1%_0.0625W_100PPM")
        (field (name "MANUFACTURER") "GENERIC")
        (field (name "AUTHOR") "CERN DEM JLC")
      )
      (libsource (lib "Resistors") (part "Resistor - 1%"))
    )
    (comp (ref "R68")
      (value "200")
      (footprint "RESC1005X40N")
      (description "Resistor - 1%")
      (fields
        (field (name "MANUFACTURER PART NUMBER") "R0402_200R_1%_0.0625W_100PPM")
        (field (name "MANUFACTURER") "GENERIC")
        (field (name "AUTHOR") "CERN DEM JLC")
      )
      (libsource (lib "Resistors") (part "Resistor - 1%"))
    )
    (comp (ref "R77")
      (value "200")
      (footprint "RESC1005X40N")
      (description "Resistor - 1%")
      (fields
        (field (name "MANUFACTURER PART NUMBER") "R0402_200R_1%_0.0625W_100PPM")
        (field (name "MANUFACTURER") "GENERIC")
        (field (name "AUTHOR") "CERN DEM JLC")
      )
      (libsource (lib "Resistors") (part "Resistor - 1%"))
    )
    (comp (ref "R78")
      (value "200")
      (footprint "RESC1005X40N")
      (description "Resistor - 1%")
      (fields
        (field (name "MANUFACTURER PART NUMBER") "R0402_200R_1%_0.0625W_100PPM")
        (field (name "MANUFACTURER") "GENERIC")
        (field (name "AUTHOR") "CERN DEM JLC")
      )
      (libsource (lib "Resistors") (part "Resistor - 1%"))
    )
    (comp (ref "R83")
      (value "200")
      (footprint "RESC1005X40N")
      (description "Resistor - 1%")
      (fields
        (field (name "MANUFACTURER PART NUMBER") "R0402_200R_1%_0.0625W_100PPM")
        (field (name "MANUFACTURER") "GENERIC")
        (field (name "AUTHOR") "CERN DEM JLC")
      )
      (libsource (lib "Resistors") (part "Resistor - 1%"))
    )
    (comp (ref "R84")
      (value "200")
      (footprint "RESC1005X40N")
      (description "Resistor - 1%")
      (fields
        (field (name "MANUFACTURER PART NUMBER") "R0402_200R_1%_0.0625W_100PPM")
        (field (name "MANUFACTURER") "GENERIC")
        (field (name "AUTHOR") "CERN DEM JLC")
      )
      (libsource (lib "Resistors") (part "Resistor - 1%"))
    )
    (comp (ref "R93")
      (value "49R9")
      (footprint "RESC1005X40N")
      (description "Resistor - 1%")
      (fields
        (field (name "MANUFACTURER PART NUMBER") "R0402_49R9_1%_0.0625W_100PPM")
        (field (name "MANUFACTURER") "GENERIC")
        (field (name "AUTHOR") "CERN DEM JLC")
      )
      (libsource (lib "Resistors") (part "Resistor - 1%"))
    )
    (comp (ref "R94")
      (value "22k")
      (footprint "RESC1005X40N")
      (description "Resistor - 1%")
      (fields
        (field (name "MANUFACTURER PART NUMBER") "R0402_22K_1%_0.0625W_100PPM")
        (field (name "MANUFACTURER") "GENERIC")
        (field (name "AUTHOR") "CERN DEM JLC")
      )
      (libsource (lib "Resistors") (part "Resistor - 1%"))
    )
    (comp (ref "R126")
      (value "Undefined")
      (footprint "RESC1005X40N")
      (description "Resistor")
      (fields (field (name "PART NUMBER") "R0402_NO-VALUE") (field (name "AUTHOR") "CERN DEM JLC"))
      (libsource (lib "Resistors") (part "Resistor"))
    )
    (comp (ref "R130")
      (value "Undefined")
      (footprint "RESC1005X40N")
      (description "Resistor")
      (fields (field (name "PART NUMBER") "R0402_NO-VALUE") (field (name "AUTHOR") "CERN DEM JLC"))
      (libsource (lib "Resistors") (part "Resistor"))
    )
    (comp (ref "R131")
      (value "Undefined")
      (footprint "RESC1005X40N")
      (description "Resistor")
      (fields (field (name "PART NUMBER") "R0402_NO-VALUE") (field (name "AUTHOR") "CERN DEM JLC"))
      (libsource (lib "Resistors") (part "Resistor"))
    )
    (comp (ref "R132")
      (value "Undefined")
      (footprint "RESC1005X40N")
      (description "Resistor")
      (fields (field (name "PART NUMBER") "R0402_NO-VALUE") (field (name "AUTHOR") "CERN DEM JLC"))
      (libsource (lib "Resistors") (part "Resistor"))
    )
    (comp (ref "R303")
      (value "33k2")
      (footprint "RESC1608X55N")
      (description "Resistor - 0.1%")
      (fields
        (field (name "MANUFACTURER PART NUMBER") "R0603_33K2_0.1%_0.063W_10PPM")
        (field (name "MANUFACTURER") "GENERIC")
        (field (name "AUTHOR") "CERN DEM JLC")
      )
      (libsource (lib "Resistors") (part "Resistor - 0.1%"))
    )
    (comp (ref "R304")
      (value "33k2")
      (footprint "RESC1608X55N")
      (description "Resistor - 0.1%")
      (fields
        (field (name "MANUFACTURER PART NUMBER") "R0603_33K2_0.1%_0.063W_10PPM")
        (field (name "MANUFACTURER") "GENERIC")
        (field (name "AUTHOR") "CERN DEM JLC")
      )
      (libsource (lib "Resistors") (part "Resistor - 0.1%"))
    )
    (comp (ref "R305")
      (value "0R02")
      (footprint "RESC3216X80N")
      (description "Resistor - 1%")
      (fields
        (field (name "MANUFACTURER PART NUMBER") "LRF1206-R020FI")
        (field (name "MANUFACTURER") "TT Electronics")
        (field (name "AUTHOR") "CERN DEM JLC")
      )
      (libsource (lib "Resistors") (part "Resistor - 1%"))
    )
    (comp (ref "R306")
      (value "0R02")
      (footprint "RESC3216X80N")
      (description "Resistor - 1%")
      (fields
        (field (name "MANUFACTURER PART NUMBER") "LRF1206-R020FI")
        (field (name "MANUFACTURER") "TT Electronics")
        (field (name "AUTHOR") "CERN DEM JLC")
      )
      (libsource (lib "Resistors") (part "Resistor - 1%"))
    )
    (comp (ref "T11")
      (value "BSS138LT1G")
      (footprint "SOT95P240X110-3N")
      (description "N-CHANNEL MOSFET WITH DIODE")
      (fields (field (name "MANUFACTURER") "ON SEMICONDUCTOR") (field (name "AUTHOR") "CERN DEM JLC"))
      (libsource (lib "ICs And Semiconductors") (part "N-MOSFET-D 1G 2S 3D"))
    )
    (comp (ref "TP58")
      (value "Test Point")
      (footprint "TPS127")
      (fields (field (name "PART NUMBER") "SMD_PAD_1.27X1.27MM") (field (name "AUTHOR") "CERN DEM JLC"))
      (libsource (lib "Eletro-mechanical") (part "Test Point"))
    )
    (comp (ref "TP59")
      (value "Test Point")
      (footprint "TPS127")
      (fields (field (name "PART NUMBER") "SMD_PAD_1.27X1.27MM") (field (name "AUTHOR") "CERN DEM JLC"))
      (libsource (lib "Eletro-mechanical") (part "Test Point"))
    )
    (comp (ref "TP60")
      (value "Test Point")
      (footprint "TPS127")
      (fields (field (name "PART NUMBER") "SMD_PAD_1.27X1.27MM") (field (name "AUTHOR") "CERN DEM JLC"))
      (libsource (lib "Eletro-mechanical") (part "Test Point"))
    )
    (comp (ref "TP61")
      (value "Test Point")
      (footprint "TPS127")
      (fields (field (name "PART NUMBER") "SMD_PAD_1.27X1.27MM") (field (name "AUTHOR") "CERN DEM JLC"))
      (libsource (lib "Eletro-mechanical") (part "Test Point"))
    )
    (comp (ref "TP62")
      (value "Test Point")
      (footprint "TPS127")
      (fields (field (name "PART NUMBER") "SMD_PAD_1.27X1.27MM") (field (name "AUTHOR") "CERN DEM JLC"))
      (libsource (lib "Eletro-mechanical") (part "Test Point"))
    )
    (comp (ref "TP73")
      (value "Test Point")
      (footprint "TPS127")
      (fields (field (name "PART NUMBER") "SMD_PAD_1.27X1.27MM") (field (name "AUTHOR") "CERN DEM JLC"))
      (libsource (lib "Eletro-mechanical") (part "Test Point"))
    )
  )
  (nets
    (net (code "3") (name "/AMC_FPGA_SYSREF0_N") (class "Default")
      (node (ref "IC58") (pin "18") (pinfunction "~{CLKOUT4}_18") (pintype "output"))
    )
    (net (code "4") (name "/AMC_FPGA_SYSREF0_P") (class "Default")
      (node (ref "IC58") (pin "17") (pinfunction "CLKOUT4_17") (pintype "output"))
    )
    (net (code "5") (name "/AMC_FPGA_SYSREF1_N") (class "Default")
      (node (ref "IC58") (pin "16") (pinfunction "~{SCLKOUT5}_16") (pintype "output"))
    )
    (net (code "6") (name "/AMC_FPGA_SYSREF1_P") (class "Default")
      (node (ref "IC58") (pin "15") (pinfunction "SCLKOUT5_15") (pintype "output"))
    )
    (net (code "7") (name "/DIAG2_N") (class "Default")
      (node (ref "C657") (pin "2") (pinfunction "2_2") (pintype "passive"))
      (node (ref "J61") (pin "1") (pinfunction "1_1") (pintype "bidirectional"))
    )
    (net (code "8") (name "/DIAG2_P") (class "Default")
      (node (ref "C656") (pin "2") (pinfunction "2_2") (pintype "passive"))
      (node (ref "J60") (pin "1") (pinfunction "1_1") (pintype "bidirectional"))
    )
    (net (code "9") (name "/HMC7043_RESET") (class "Default")
      (node (ref "IC58") (pin "5") (pinfunction "RESET_5") (pintype "input"))
    )
    (net (code "10") (name "/HMC7043_SLEN") (class "Default")
      (node (ref "IC58") (pin "31") (pinfunction "SLEN_31") (pintype "bidirectional"))
      (node (ref "TP58") (pin "1") (pinfunction "1_1") (pintype "bidirectional"))
    )
    (net (code "11") (name "/HMC_7043_OUT_EN") (class "Default")
      (node (ref "R94") (pin "2") (pinfunction "2_2") (pintype "passive"))
      (node (ref "T11") (pin "1") (pinfunction "G_1") (pintype "passive"))
      (node (ref "TP62") (pin "1") (pinfunction "1_1") (pintype "bidirectional"))
    )
    (net (code "12") (name "/HMC_SPI_GPIO") (class "Default")
      (node (ref "IC58") (pin "34") (pinfunction "GPIO_34") (pintype "bidirectional"))
      (node (ref "TP61") (pin "1") (pinfunction "1_1") (pintype "bidirectional"))
    )
    (net (code "13") (name "/HMC_SPI_SCLK") (class "Default")
      (node (ref "IC58") (pin "32") (pinfunction "SCLK_32") (pintype "bidirectional"))
      (node (ref "TP59") (pin "1") (pinfunction "1_1") (pintype "bidirectional"))
    )
    (net (code "14") (name "/HMC_SPI_SDATA") (class "Default")
      (node (ref "IC58") (pin "33") (pinfunction "SDATA_33") (pintype "bidirectional"))
      (node (ref "TP60") (pin "1") (pinfunction "1_1") (pintype "bidirectional"))
    )
    (net (code "15") (name "/P3V3_CLKDIS5_1") (class "Default")
      (node (ref "C917") (pin "2") (pinfunction "2_2") (pintype "passive"))
      (node (ref "IC62") (pin "10") (pinfunction "OUT_10") (pintype "output"))
      (node (ref "IC62") (pin "9") (pinfunction "OUTS_9") (pintype "output"))
      (node (ref "R305") (pin "1") (pinfunction "1_1") (pintype "passive"))
    )
    (net (code "16") (name "/P3V3_CLKDIS5_2") (class "Default")
      (node (ref "C918") (pin "2") (pinfunction "2_2") (pintype "passive"))
      (node (ref "IC63") (pin "10") (pinfunction "OUT_10") (pintype "output"))
      (node (ref "IC63") (pin "9") (pinfunction "OUTS_9") (pintype "output"))
      (node (ref "R306") (pin "1") (pinfunction "1_1") (pintype "passive"))
    )
    (net (code "17") (name "/P4V0_LDO_IN5") (class "Default")
      (node (ref "C916") (pin "2") (pinfunction "2_2") (pintype "passive"))
      (node (ref "IC62") (pin "1") (pinfunction "IN_1") (pintype "input"))
      (node (ref "IC62") (pin "2") (pinfunction "IN_2") (pintype "input"))
      (node (ref "IC62") (pin "3") (pinfunction "EN/UV_3") (pintype "input"))
      (node (ref "IC62") (pin "6") (pinfunction "PGFB_6") (pintype "input"))
      (node (ref "IC63") (pin "1") (pinfunction "IN_1") (pintype "input"))
      (node (ref "IC63") (pin "2") (pinfunction "IN_2") (pintype "input"))
      (node (ref "IC63") (pin "3") (pinfunction "EN/UV_3") (pintype "input"))
      (node (ref "IC63") (pin "6") (pinfunction "PGFB_6") (pintype "input"))
      (node (ref "L89") (pin "2") (pinfunction "2_2") (pintype "passive"))
    )
    (net (code "18") (name "/REFSYNCIN_N") (class "Default")
      (node (ref "C112") (pin "2") (pinfunction "2_2") (pintype "passive"))
      (node (ref "IC58") (pin "29") (pinfunction "~{RFSYNCIN}_29") (pintype "input"))
    )
    (net (code "19") (name "/REFSYNCIN_P") (class "Default")
      (node (ref "C108") (pin "2") (pinfunction "2_2") (pintype "passive"))
      (node (ref "IC58") (pin "28") (pinfunction "RFSYNCIN_28") (pintype "input"))
    )
    (net (code "20") (name "/RF_D_N") (class "Default")
      (node (ref "C437") (pin "2") (pinfunction "2_2") (pintype "passive"))
      (node (ref "IC58") (pin "25") (pinfunction "~{CLKIN}_25") (pintype "input"))
    )
    (net (code "21") (name "/RF_D_P") (class "Default")
      (node (ref "C436") (pin "2") (pinfunction "2_2") (pintype "passive"))
      (node (ref "IC58") (pin "26") (pinfunction "CLKIN_26") (pintype "input"))
    )
    (net (code "22") (name "/VCC1_CLKDIST") (class "Default")
      (node (ref "C396") (pin "2") (pinfunction "2_2") (pintype "passive"))
      (node (ref "C397") (pin "2") (pinfunction "2_2") (pintype "passive"))
      (node (ref "C850") (pin "1") (pinfunction "1_1") (pintype "passive"))
      (node (ref "IC58") (pin "8") (pinfunction "VCC1_CLKDIST_8") (pintype "power_in"))
      (node (ref "L46") (pin "2") (pinfunction "2_2") (pintype "passive"))
    )
    (net (code "23") (name "/VCC2_OUT") (class "Default")
      (node (ref "C398") (pin "2") (pinfunction "2_2") (pintype "passive"))
      (node (ref "C399") (pin "2") (pinfunction "2_2") (pintype "passive"))
      (node (ref "C851") (pin "1") (pinfunction "1_1") (pintype "passive"))
      (node (ref "IC58") (pin "13") (pinfunction "VCC2_OUT_13") (pintype "power_in"))
      (node (ref "L47") (pin "2") (pinfunction "2_2") (pintype "passive"))
    )
    (net (code "24") (name "/VCC3_OUT") (class "Default")
      (node (ref "C404") (pin "2") (pinfunction "2_2") (pintype "passive"))
      (node (ref "C405") (pin "2") (pinfunction "2_2") (pintype "passive"))
      (node (ref "C854") (pin "1") (pinfunction "1_1") (pintype "passive"))
      (node (ref "IC58") (pin "19") (pinfunction "VCC3_OUT_19") (pintype "power_in"))
      (node (ref "L50") (pin "2") (pinfunction "2_2") (pintype "passive"))
    )
    (net (code "25") (name "/VCC3_SYSREF") (class "Default")
      (node (ref "C402") (pin "2") (pinfunction "2_2") (pintype "passive"))
      (node (ref "C403") (pin "2") (pinfunction "2_2") (pintype "passive"))
      (node (ref "C853") (pin "1") (pinfunction "1_1") (pintype "passive"))
      (node (ref "IC58") (pin "30") (pinfunction "VCC5_SYSREF_30") (pintype "power_in"))
      (node (ref "L49") (pin "2") (pinfunction "2_2") (pintype "passive"))
    )
    (net (code "26") (name "/VCC4_CLKIN") (class "Default")
      (node (ref "C394") (pin "2") (pinfunction "2_2") (pintype "passive"))
      (node (ref "C395") (pin "2") (pinfunction "2_2") (pintype "passive"))
      (node (ref "C849") (pin "1") (pinfunction "1_1") (pintype "passive"))
      (node (ref "IC58") (pin "27") (pinfunction "VCC4_CLKIN_27") (pintype "power_in"))
      (node (ref "L45") (pin "2") (pinfunction "2_2") (pintype "passive"))
    )
    (net (code "27") (name "/VCC6_OUT") (class "Default")
      (node (ref "C406") (pin "2") (pinfunction "2_2") (pintype "passive"))
      (node (ref "C407") (pin "2") (pinfunction "2_2") (pintype "passive"))
      (node (ref "C855") (pin "1") (pinfunction "1_1") (pintype "passive"))
      (node (ref "IC58") (pin "39") (pinfunction "VCC6_OUT_39") (pintype "power_in"))
      (node (ref "L51") (pin "2") (pinfunction "2_2") (pintype "passive"))
    )
    (net (code "28") (name "/VCC7_OUT") (class "Default")
      (node (ref "C400") (pin "2") (pinfunction "2_2") (pintype "passive"))
      (node (ref "C401") (pin "2") (pinfunction "2_2") (pintype "passive"))
      (node (ref "C852") (pin "1") (pinfunction "1_1") (pintype "passive"))
      (node (ref "IC58") (pin "48") (pinfunction "VCC7_OUT_48") (pintype "power_in"))
      (node (ref "L48") (pin "2") (pinfunction "2_2") (pintype "passive"))
    )
    (net (code "29") (name "/VCC_CLOCKOUT1") (class "Default")
      (node (ref "C388") (pin "2") (pinfunction "2_2") (pintype "passive"))
      (node (ref "C389") (pin "2") (pinfunction "2_2") (pintype "passive"))
      (node (ref "C846") (pin "1") (pinfunction "1_1") (pintype "passive"))
      (node (ref "L42") (pin "2") (pinfunction "2_2") (pintype "passive"))
      (node (ref "L47") (pin "1") (pinfunction "1_1") (pintype "passive"))
      (node (ref "L48") (pin "1") (pinfunction "1_1") (pintype "passive"))
    )
    (net (code "30") (name "/VCC_CLOCKOUT2") (class "Default")
      (node (ref "C390") (pin "2") (pinfunction "2_2") (pintype "passive"))
      (node (ref "C391") (pin "2") (pinfunction "2_2") (pintype "passive"))
      (node (ref "C847") (pin "1") (pinfunction "1_1") (pintype "passive"))
      (node (ref "L43") (pin "2") (pinfunction "2_2") (pintype "passive"))
      (node (ref "L49") (pin "1") (pinfunction "1_1") (pintype "passive"))
      (node (ref "L50") (pin "1") (pinfunction "1_1") (pintype "passive"))
    )
    (net (code "31") (name "/VCC_CLOCKOUT3") (class "Default")
      (node (ref "C392") (pin "2") (pinfunction "2_2") (pintype "passive"))
      (node (ref "C393") (pin "2") (pinfunction "2_2") (pintype "passive"))
      (node (ref "C848") (pin "1") (pinfunction "1_1") (pintype "passive"))
      (node (ref "L44") (pin "2") (pinfunction "2_2") (pintype "passive"))
      (node (ref "L51") (pin "1") (pinfunction "1_1") (pintype "passive"))
    )
    (net (code "32") (name "/VCC_PLL") (class "Default")
      (node (ref "C386") (pin "2") (pinfunction "2_2") (pintype "passive"))
      (node (ref "C387") (pin "2") (pinfunction "2_2") (pintype "passive"))
      (node (ref "C845") (pin "1") (pinfunction "1_1") (pintype "passive"))
      (node (ref "L41") (pin "2") (pinfunction "2_2") (pintype "passive"))
      (node (ref "L45") (pin "1") (pinfunction "1_1") (pintype "passive"))
      (node (ref "L46") (pin "1") (pinfunction "1_1") (pintype "passive"))
    )
    (net (code "35") (name "GND") (class "Default")
      (node (ref "C386") (pin "1") (pinfunction "1_1") (pintype "passive"))
      (node (ref "C387") (pin "1") (pinfunction "1_1") (pintype "passive"))
      (node (ref "C388") (pin "1") (pinfunction "1_1") (pintype "passive"))
      (node (ref "C389") (pin "1") (pinfunction "1_1") (pintype "passive"))
      (node (ref "C390") (pin "1") (pinfunction "1_1") (pintype "passive"))
      (node (ref "C391") (pin "1") (pinfunction "1_1") (pintype "passive"))
      (node (ref "C392") (pin "1") (pinfunction "1_1") (pintype "passive"))
      (node (ref "C393") (pin "1") (pinfunction "1_1") (pintype "passive"))
      (node (ref "C394") (pin "1") (pinfunction "1_1") (pintype "passive"))
      (node (ref "C395") (pin "1") (pinfunction "1_1") (pintype "passive"))
      (node (ref "C396") (pin "1") (pinfunction "1_1") (pintype "passive"))
      (node (ref "C397") (pin "1") (pinfunction "1_1") (pintype "passive"))
      (node (ref "C398") (pin "1") (pinfunction "1_1") (pintype "passive"))
      (node (ref "C399") (pin "1") (pinfunction "1_1") (pintype "passive"))
      (node (ref "C400") (pin "1") (pinfunction "1_1") (pintype "passive"))
      (node (ref "C401") (pin "1") (pinfunction "1_1") (pintype "passive"))
      (node (ref "C402") (pin "1") (pinfunction "1_1") (pintype "passive"))
      (node (ref "C403") (pin "1") (pinfunction "1_1") (pintype "passive"))
      (node (ref "C404") (pin "1") (pinfunction "1_1") (pintype "passive"))
      (node (ref "C405") (pin "1") (pinfunction "1_1") (pintype "passive"))
      (node (ref "C406") (pin "1") (pinfunction "1_1") (pintype "passive"))
      (node (ref "C407") (pin "1") (pinfunction "1_1") (pintype "passive"))
      (node (ref "C6") (pin "1") (pinfunction "1_1") (pintype "passive"))
      (node (ref "C674") (pin "1") (pinfunction "1_1") (pintype "passive"))
      (node (ref "C675") (pin "1") (pinfunction "1_1") (pintype "passive"))
      (node (ref "C7") (pin "1") (pinfunction "1_1") (pintype "passive"))
      (node (ref "C8") (pin "1") (pinfunction "1_1") (pintype "passive"))
      (node (ref "C845") (pin "2") (pinfunction "2_2") (pintype "passive"))
      (node (ref "C846") (pin "2") (pinfunction "2_2") (pintype "passive"))
      (node (ref "C847") (pin "2") (pinfunction "2_2") (pintype "passive"))
      (node (ref "C848") (pin "2") (pinfunction "2_2") (pintype "passive"))
      (node (ref "C849") (pin "2") (pinfunction "2_2") (pintype "passive"))
      (node (ref "C850") (pin "2") (pinfunction "2_2") (pintype "passive"))
      (node (ref "C851") (pin "2") (pinfunction "2_2") (pintype "passive"))
      (node (ref "C852") (pin "2") (pinfunction "2_2") (pintype "passive"))
      (node (ref "C853") (pin "2") (pinfunction "2_2") (pintype "passive"))
      (node (ref "C854") (pin "2") (pinfunction "2_2") (pintype "passive"))
      (node (ref "C855") (pin "2") (pinfunction "2_2") (pintype "passive"))
      (node (ref "C916") (pin "1") (pinfunction "1_1") (pintype "passive"))
      (node (ref "C917") (pin "1") (pinfunction "1_1") (pintype "passive"))
      (node (ref "C918") (pin "1") (pinfunction "1_1") (pintype "passive"))
      (node (ref "C929") (pin "2") (pinfunction "2_2") (pintype "passive"))
      (node (ref "IC58") (pin "14") (pinfunction "RSV_14") (pintype "passive"))
      (node (ref "IC58") (pin "24") (pinfunction "RSV_24") (pintype "passive"))
      (node (ref "IC58") (pin "49") (pinfunction "EP_49") (pintype "power_in"))
      (node (ref "IC62") (pin "11") (pinfunction "GND_11") (pintype "power_in"))
      (node (ref "IC62") (pin "5") (pinfunction "ILIM_5") (pintype "input"))
      (node (ref "IC62") (pin "8") (pinfunction "GND_8") (pintype "power_in"))
      (node (ref "IC63") (pin "11") (pinfunction "GND_11") (pintype "power_in"))
      (node (ref "IC63") (pin "5") (pinfunction "ILIM_5") (pintype "input"))
      (node (ref "IC63") (pin "8") (pinfunction "GND_8") (pintype "power_in"))
      (node (ref "J60") (pin "2") (pinfunction "2_2") (pintype "bidirectional"))
      (node (ref "J61") (pin "2") (pinfunction "2_2") (pintype "bidirectional"))
      (node (ref "J7") (pin "2") (pinfunction "2_2") (pintype "bidirectional"))
      (node (ref "J8") (pin "2") (pinfunction "2_2") (pintype "bidirectional"))
      (node (ref "R126") (pin "2") (pinfunction "2_2") (pintype "passive"))
      (node (ref "R130") (pin "2") (pinfunction "2_2") (pintype "passive"))
      (node (ref "R131") (pin "2") (pinfunction "2_2") (pintype "passive"))
      (node (ref "R132") (pin "2") (pinfunction "2_2") (pintype "passive"))
      (node (ref "R303") (pin "1") (pinfunction "1_1") (pintype "passive"))
      (node (ref "R304") (pin "1") (pinfunction "1_1") (pintype "passive"))
      (node (ref "R61") (pin "2") (pinfunction "2_2") (pintype "passive"))
      (node (ref "R62") (pin "2") (pinfunction "2_2") (pintype "passive"))
      (node (ref "R63") (pin "2") (pinfunction "2_2") (pintype "passive"))
      (node (ref "R64") (pin "2") (pinfunction "2_2") (pintype "passive"))
      (node (ref "R65") (pin "2") (pinfunction "2_2") (pintype "passive"))
      (node (ref "R66") (pin "2") (pinfunction "2_2") (pintype "passive"))
      (node (ref "R67") (pin "2") (pinfunction "2_2") (pintype "passive"))
      (node (ref "R68") (pin "2") (pinfunction "2_2") (pintype "passive"))
      (node (ref "R83") (pin "2") (pinfunction "2_2") (pintype "passive"))
      (node (ref "R84") (pin "2") (pinfunction "2_2") (pintype "passive"))
      (node (ref "R94") (pin "1") (pinfunction "1_1") (pintype "passive"))
      (node (ref "T11") (pin "2") (pinfunction "S_2") (pintype "passive"))
    )
    (net (code "36") (name "Net-(C108-Pad1)") (class "Default")
      (node (ref "C108") (pin "1") (pinfunction "1_1") (pintype "passive"))
      (node (ref "J7") (pin "1") (pinfunction "1_1") (pintype "bidirectional"))
    )
    (net (code "37") (name "Net-(C112-Pad1)") (class "Default")
      (node (ref "C112") (pin "1") (pinfunction "1_1") (pintype "passive"))
      (node (ref "J8") (pin "1") (pinfunction "1_1") (pintype "bidirectional"))
    )
    (net (code "38") (name "Net-(C369-Pad2)") (class "Default")
      (node (ref "C369") (pin "2") (pinfunction "2_2") (pintype "passive"))
      (node (ref "R33") (pin "1") (pinfunction "1_1") (pintype "passive"))
    )
    (net (code "39") (name "Net-(C370-Pad2)") (class "Default")
      (node (ref "C370") (pin "2") (pinfunction "2_2") (pintype "passive"))
      (node (ref "R93") (pin "1") (pinfunction "1_1") (pintype "passive"))
    )
    (net (code "40") (name "Net-(IC58-BGAPBYP1)") (class "Default")
      (node (ref "C675") (pin "2") (pinfunction "2_2") (pintype "passive"))
      (node (ref "IC58") (pin "6") (pinfunction "BGAPBYP1_6") (pintype "passive"))
    )
    (net (code "41") (name "Net-(IC58-CLKOUT0)") (class "Default")
      (node (ref "C353") (pin "1") (pinfunction "1_1") (pintype "passive"))
      (node (ref "IC58") (pin "1") (pinfunction "CLKOUT0_1") (pintype "output"))
      (node (ref "R62") (pin "1") (pinfunction "1_1") (pintype "passive"))
    )
    (net (code "42") (name "Net-(IC58-CLKOUT2)") (class "Default")
      (node (ref "C357") (pin "1") (pinfunction "1_1") (pintype "passive"))
      (node (ref "IC58") (pin "11") (pinfunction "CLKOUT2_11") (pintype "output"))
      (node (ref "R66") (pin "1") (pinfunction "1_1") (pintype "passive"))
    )
    (net (code "43") (name "Net-(IC58-CLKOUT8)") (class "Default")
      (node (ref "C369") (pin "1") (pinfunction "1_1") (pintype "passive"))
      (node (ref "IC58") (pin "37") (pinfunction "CLKOUT8_37") (pintype "output"))
      (node (ref "R78") (pin "1") (pinfunction "1_1") (pintype "passive"))
    )
    (net (code "44") (name "Net-(IC58-LDOBYP2)") (class "Default")
      (node (ref "C674") (pin "2") (pinfunction "2_2") (pintype "passive"))
      (node (ref "IC58") (pin "7") (pinfunction "LDOBYP2_7") (pintype "passive"))
    )
    (net (code "45") (name "Net-(IC58-SCLKOUT1)") (class "Default")
      (node (ref "IC58") (pin "3") (pinfunction "SCLKOUT1_3") (pintype "output"))
      (node (ref "R39") (pin "1") (pinfunction "1_1") (pintype "passive"))
      (node (ref "R64") (pin "1") (pinfunction "1_1") (pintype "passive"))
    )
    (net (code "46") (name "Net-(IC58-SCLKOUT3)") (class "Default")
      (node (ref "IC58") (pin "9") (pinfunction "SCLKOUT3_9") (pintype "output"))
      (node (ref "R57") (pin "1") (pinfunction "1_1") (pintype "passive"))
      (node (ref "R68") (pin "1") (pinfunction "1_1") (pintype "passive"))
    )
    (net (code "47") (name "Net-(IC58-SCLKOUT11)") (class "Default")
      (node (ref "C656") (pin "1") (pinfunction "1_1") (pintype "passive"))
      (node (ref "IC58") (pin "42") (pinfunction "SCLKOUT11_42") (pintype "output"))
      (node (ref "R84") (pin "1") (pinfunction "1_1") (pintype "passive"))
    )
    (net (code "48") (name "Net-(IC58-~{CLKOUT0})") (class "Default")
      (node (ref "C354") (pin "1") (pinfunction "1_1") (pintype "passive"))
      (node (ref "IC58") (pin "2") (pinfunction "~{CLKOUT0}_2") (pintype "output"))
      (node (ref "R61") (pin "1") (pinfunction "1_1") (pintype "passive"))
    )
    (net (code "49") (name "Net-(IC58-~{CLKOUT2})") (class "Default")
      (node (ref "C358") (pin "1") (pinfunction "1_1") (pintype "passive"))
      (node (ref "IC58") (pin "12") (pinfunction "~{CLKOUT2}_12") (pintype "output"))
      (node (ref "R65") (pin "1") (pinfunction "1_1") (pintype "passive"))
    )
    (net (code "50") (name "Net-(IC58-~{CLKOUT8})") (class "Default")
      (node (ref "C370") (pin "1") (pinfunction "1_1") (pintype "passive"))
      (node (ref "IC58") (pin "38") (pinfunction "~{CLKOUT8}_38") (pintype "output"))
      (node (ref "R77") (pin "1") (pinfunction "1_1") (pintype "passive"))
    )
    (net (code "51") (name "Net-(IC58-~{SCLKOUT1})") (class "Default")
      (node (ref "IC58") (pin "4") (pinfunction "~{SCLKOUT1}_4") (pintype "output"))
      (node (ref "R56") (pin "1") (pinfunction "1_1") (pintype "passive"))
      (node (ref "R63") (pin "1") (pinfunction "1_1") (pintype "passive"))
    )
    (net (code "52") (name "Net-(IC58-~{SCLKOUT3})") (class "Default")
      (node (ref "IC58") (pin "10") (pinfunction "~{SCLKOUT3}_10") (pintype "output"))
      (node (ref "R58") (pin "1") (pinfunction "1_1") (pintype "passive"))
      (node (ref "R67") (pin "1") (pinfunction "1_1") (pintype "passive"))
    )
    (net (code "53") (name "Net-(IC58-~{SCLKOUT11})") (class "Default")
      (node (ref "C657") (pin "1") (pinfunction "1_1") (pintype "passive"))
      (node (ref "IC58") (pin "43") (pinfunction "~{SCLKOUT11}_43") (pintype "output"))
      (node (ref "R83") (pin "1") (pinfunction "1_1") (pintype "passive"))
    )
    (net (code "54") (name "Net-(IC62-SET)") (class "Default")
      (node (ref "C929") (pin "1") (pinfunction "1_1") (pintype "passive"))
      (node (ref "IC62") (pin "7") (pinfunction "SET_7") (pintype "input"))
      (node (ref "IC63") (pin "7") (pinfunction "SET_7") (pintype "input"))
      (node (ref "R303") (pin "2") (pinfunction "2_2") (pintype "passive"))
      (node (ref "R304") (pin "2") (pinfunction "2_2") (pintype "passive"))
    )
    (net (code "55") (name "Net-(R126-Pad1)") (class "Default")
      (node (ref "R126") (pin "1") (pinfunction "1_1") (pintype "passive"))
      (node (ref "R39") (pin "2") (pinfunction "2_2") (pintype "passive"))
    )
    (net (code "56") (name "Net-(R130-Pad1)") (class "Default")
      (node (ref "R130") (pin "1") (pinfunction "1_1") (pintype "passive"))
      (node (ref "R56") (pin "2") (pinfunction "2_2") (pintype "passive"))
    )
    (net (code "57") (name "Net-(R131-Pad1)") (class "Default")
      (node (ref "R131") (pin "1") (pinfunction "1_1") (pintype "passive"))
      (node (ref "R57") (pin "2") (pinfunction "2_2") (pintype "passive"))
    )
    (net (code "58") (name "Net-(R132-Pad1)") (class "Default")
      (node (ref "R132") (pin "1") (pinfunction "1_1") (pintype "passive"))
      (node (ref "R58") (pin "2") (pinfunction "2_2") (pintype "passive"))
    )
    (net (code "59") (name "Net-(T11-D)") (class "Default")
      (node (ref "C6") (pin "2") (pinfunction "2_2") (pintype "passive"))
      (node (ref "C7") (pin "2") (pinfunction "2_2") (pintype "passive"))
      (node (ref "C8") (pin "2") (pinfunction "2_2") (pintype "passive"))
      (node (ref "R77") (pin "2") (pinfunction "2_2") (pintype "passive"))
      (node (ref "R78") (pin "2") (pinfunction "2_2") (pintype "passive"))
      (node (ref "T11") (pin "3") (pinfunction "D_3") (pintype "passive"))
    )
    (net (code "60") (name "P3V3_CLKDIS1") (class "Default")
      (node (ref "L41") (pin "1") (pinfunction "1_1") (pintype "passive"))
      (node (ref "L42") (pin "1") (pinfunction "1_1") (pintype "passive"))
      (node (ref "L43") (pin "1") (pinfunction "1_1") (pintype "passive"))
      (node (ref "L44") (pin "1") (pinfunction "1_1") (pintype "passive"))
      (node (ref "R305") (pin "2") (pinfunction "2_2") (pintype "passive"))
      (node (ref "R306") (pin "2") (pinfunction "2_2") (pintype "passive"))
      (node (ref "TP73") (pin "1") (pinfunction "1_1") (pintype "bidirectional"))
    )
    (net (code "61") (name "P4V0") (class "Default")
      (node (ref "L89") (pin "1") (pinfunction "1_1") (pintype "passive"))
    )
    (net (code "62") (name "unconnected-(C353-Pad2)") (class "Default")
      (node (ref "C353") (pin "2") (pinfunction "2_2") (pintype "passive"))
    )
    (net (code "63") (name "unconnected-(C354-Pad2)") (class "Default")
      (node (ref "C354") (pin "2") (pinfunction "2_2") (pintype "passive"))
    )
    (net (code "64") (name "unconnected-(C357-Pad2)") (class "Default")
      (node (ref "C357") (pin "2") (pinfunction "2_2") (pintype "passive"))
    )
    (net (code "65") (name "unconnected-(C358-Pad2)") (class "Default")
      (node (ref "C358") (pin "2") (pinfunction "2_2") (pintype "passive"))
    )
    (net (code "66") (name "unconnected-(C436-Pad1)") (class "Default")
      (node (ref "C436") (pin "1") (pinfunction "1_1") (pintype "passive"))
    )
    (net (code "67") (name "unconnected-(C437-Pad1)") (class "Default")
      (node (ref "C437") (pin "1") (pinfunction "1_1") (pintype "passive"))
    )
    (net (code "68") (name "unconnected-(IC58-CLKOUT6-Pad20)") (class "Default")
      (node (ref "IC58") (pin "20") (pinfunction "CLKOUT6_20") (pintype "output"))
    )
    (net (code "69") (name "unconnected-(IC58-CLKOUT10-Pad40)") (class "Default")
      (node (ref "IC58") (pin "40") (pinfunction "CLKOUT10_40") (pintype "output"))
    )
    (net (code "70") (name "unconnected-(IC58-CLKOUT12-Pad46)") (class "Default")
      (node (ref "IC58") (pin "46") (pinfunction "CLKOUT12_46") (pintype "output"))
    )
    (net (code "71") (name "unconnected-(IC58-SCLKOUT7-Pad22)") (class "Default")
      (node (ref "IC58") (pin "22") (pinfunction "SCLKOUT7_22") (pintype "output"))
    )
    (net (code "72") (name "unconnected-(IC58-SCLKOUT9-Pad35)") (class "Default")
      (node (ref "IC58") (pin "35") (pinfunction "SCLKOUT9_35") (pintype "output"))
    )
    (net (code "73") (name "unconnected-(IC58-SCLKOUT13-Pad44)") (class "Default")
      (node (ref "IC58") (pin "44") (pinfunction "SCLKOUT13_44") (pintype "output"))
    )
    (net (code "74") (name "unconnected-(IC58-~{CLKOUT6}-Pad21)") (class "Default")
      (node (ref "IC58") (pin "21") (pinfunction "~{CLKOUT6}_21") (pintype "output"))
    )
    (net (code "75") (name "unconnected-(IC58-~{CLKOUT10}-Pad41)") (class "Default")
      (node (ref "IC58") (pin "41") (pinfunction "~{CLKOUT10}_41") (pintype "output"))
    )
    (net (code "76") (name "unconnected-(IC58-~{CLKOUT12}-Pad47)") (class "Default")
      (node (ref "IC58") (pin "47") (pinfunction "~{CLKOUT12}_47") (pintype "output"))
    )
    (net (code "77") (name "unconnected-(IC58-~{SCLKOUT7}-Pad23)") (class "Default")
      (node (ref "IC58") (pin "23") (pinfunction "~{SCLKOUT7}_23") (pintype "output"))
    )
    (net (code "78") (name "unconnected-(IC58-~{SCLKOUT9}-Pad36)") (class "Default")
      (node (ref "IC58") (pin "36") (pinfunction "~{SCLKOUT9}_36") (pintype "output"))
    )
    (net (code "79") (name "unconnected-(IC58-~{SCLKOUT13}-Pad45)") (class "Default")
      (node (ref "IC58") (pin "45") (pinfunction "~{SCLKOUT13}_45") (pintype "output"))
    )
    (net (code "80") (name "unconnected-(IC62-PG-Pad4)") (class "Default")
      (node (ref "IC62") (pin "4") (pinfunction "PG_4") (pintype "output"))
    )
    (net (code "81") (name "unconnected-(IC63-PG-Pad4)") (class "Default")
      (node (ref "IC63") (pin "4") (pinfunction "PG_4") (pintype "output"))
    )
    (net (code "82") (name "unconnected-(R33-Pad2)") (class "Default")
      (node (ref "R33") (pin "2") (pinfunction "2_2") (pintype "passive"))
    )
    (net (code "83") (name "unconnected-(R93-Pad2)") (class "Default")
      (node (ref "R93") (pin "2") (pinfunction "2_2") (pintype "passive"))
    )
  )
)
